# HW1_62.net
KiCad netlist of a schematic drawn in EasyEDA
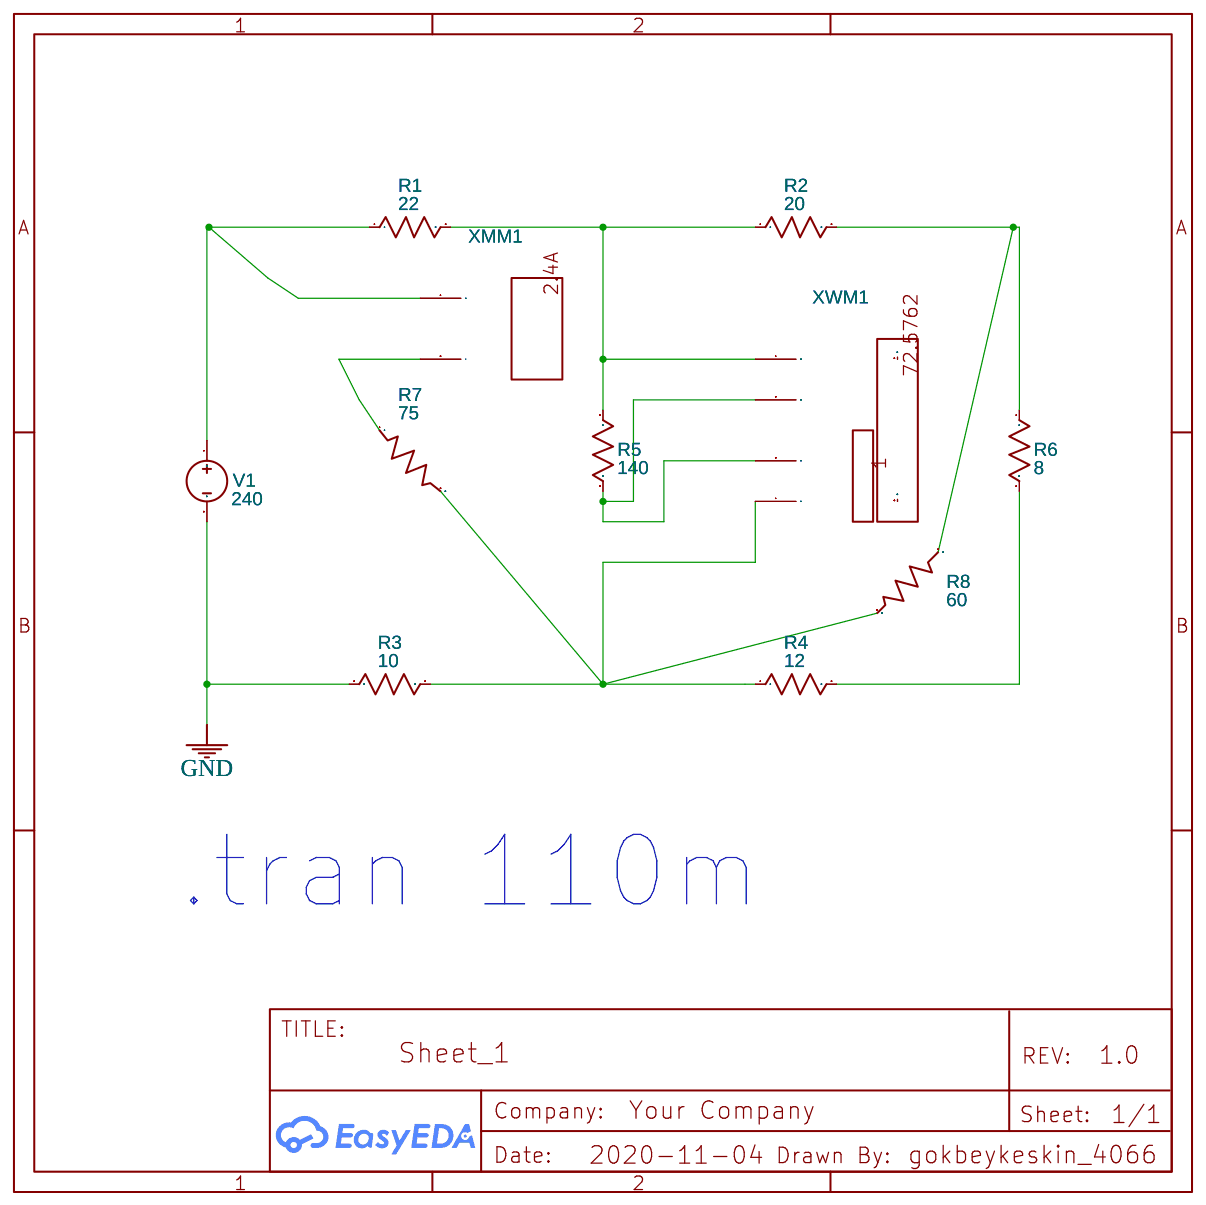
[diagram p0: schematic sheet]

(export (version "E")
  (design (tool "Eeschema 10.0.6"))
  (components
    (comp (ref "R1") (value "22") (libsource (lib "") (part "Resistor_US_1")))
    (comp (ref "R2") (value "20") (libsource (lib "") (part "Resistor_US_1")))
    (comp (ref "R3") (value "10") (libsource (lib "") (part "Resistor_US_1")))
    (comp (ref "R4") (value "12") (libsource (lib "") (part "Resistor_US_1")))
    (comp (ref "R5") (value "140") (libsource (lib "") (part "Resistor_US")))
    (comp (ref "R6") (value "8") (libsource (lib "") (part "Resistor_US")))
    (comp (ref "R7") (value "75") (libsource (lib "") (part "Resistor_45Degree_US")))
    (comp (ref "R8") (value "60") (libsource (lib "") (part "Resistor_45Degree_US_1")))
    (comp (ref "V1") (value "240") (libsource (lib "") (part "VDC")))
    (comp (ref "XMM1") (value "Multimeter") (libsource (lib "") (part "MULTIMETER")))
    (comp (ref "XWM1") (value "Wattmeter") (libsource (lib "") (part "WATTMETER")))
  )
  (nets
    (net (code "1") (name "GND") (class "Default")
      (node (ref "R3") (pin "1") (pinfunction "1_1") (pintype "unspecified"))
      (node (ref "V1") (pin "2") (pinfunction "2_2") (pintype "unspecified"))
    )
    (net (code "2") (name "Net-(R2-Pad2)") (class "Default")
      (node (ref "R2") (pin "2") (pinfunction "2_2") (pintype "unspecified"))
      (node (ref "R6") (pin "1") (pinfunction "1_1") (pintype "unspecified"))
      (node (ref "R8") (pin "1") (pinfunction "1_1") (pintype "unspecified"))
    )
    (net (code "3") (name "Net-(R4-Pad2)") (class "Default")
      (node (ref "R4") (pin "2") (pinfunction "2_2") (pintype "unspecified"))
      (node (ref "R6") (pin "2") (pinfunction "2_2") (pintype "unspecified"))
    )
    (net (code "4") (name "Net-(XMM1-+)") (class "Default")
      (node (ref "R1") (pin "1") (pinfunction "1_1") (pintype "unspecified"))
      (node (ref "V1") (pin "1") (pinfunction "1_1") (pintype "unspecified"))
      (node (ref "XMM1") (pin "1") (pinfunction "+_1") (pintype "unspecified"))
    )
    (net (code "5") (name "Net-(XMM1-I)") (class "Default")
      (node (ref "R7") (pin "1") (pinfunction "1_1") (pintype "unspecified"))
      (node (ref "XMM1") (pin "2") (pinfunction "I_2") (pintype "unspecified"))
    )
    (net (code "6") (name "Net-(XWM1-I+)") (class "Default")
      (node (ref "R5") (pin "2") (pinfunction "2_2") (pintype "unspecified"))
      (node (ref "XWM1") (pin "2") (pinfunction "V-_2") (pintype "unspecified"))
      (node (ref "XWM1") (pin "3") (pinfunction "I+_3") (pintype "unspecified"))
    )
    (net (code "7") (name "Net-(XWM1-I-)") (class "Default")
      (node (ref "R3") (pin "2") (pinfunction "2_2") (pintype "unspecified"))
      (node (ref "R4") (pin "1") (pinfunction "1_1") (pintype "unspecified"))
      (node (ref "R7") (pin "2") (pinfunction "2_2") (pintype "unspecified"))
      (node (ref "R8") (pin "2") (pinfunction "2_2") (pintype "unspecified"))
      (node (ref "XWM1") (pin "4") (pinfunction "I-_4") (pintype "unspecified"))
    )
    (net (code "8") (name "Net-(XWM1-V+)") (class "Default")
      (node (ref "R1") (pin "2") (pinfunction "2_2") (pintype "unspecified"))
      (node (ref "R2") (pin "1") (pinfunction "1_1") (pintype "unspecified"))
      (node (ref "R5") (pin "1") (pinfunction "1_1") (pintype "unspecified"))
      (node (ref "XWM1") (pin "1") (pinfunction "V+_1") (pintype "unspecified"))
    )
    (net (code "9") (name "unconnected-(XWM1-PadP)") (class "Default")
      (node (ref "XWM1") (pin "P") (pinfunction "P_P") (pintype "unspecified"))
    )
    (net (code "10") (name "unconnected-(XWM1-PadPF)") (class "Default")
      (node (ref "XWM1") (pin "PF") (pinfunction "PF_PF") (pintype "unspecified"))
    )
  )
)
